# cmv_s.net
KiCad netlist of a schematic drawn in EAGLE
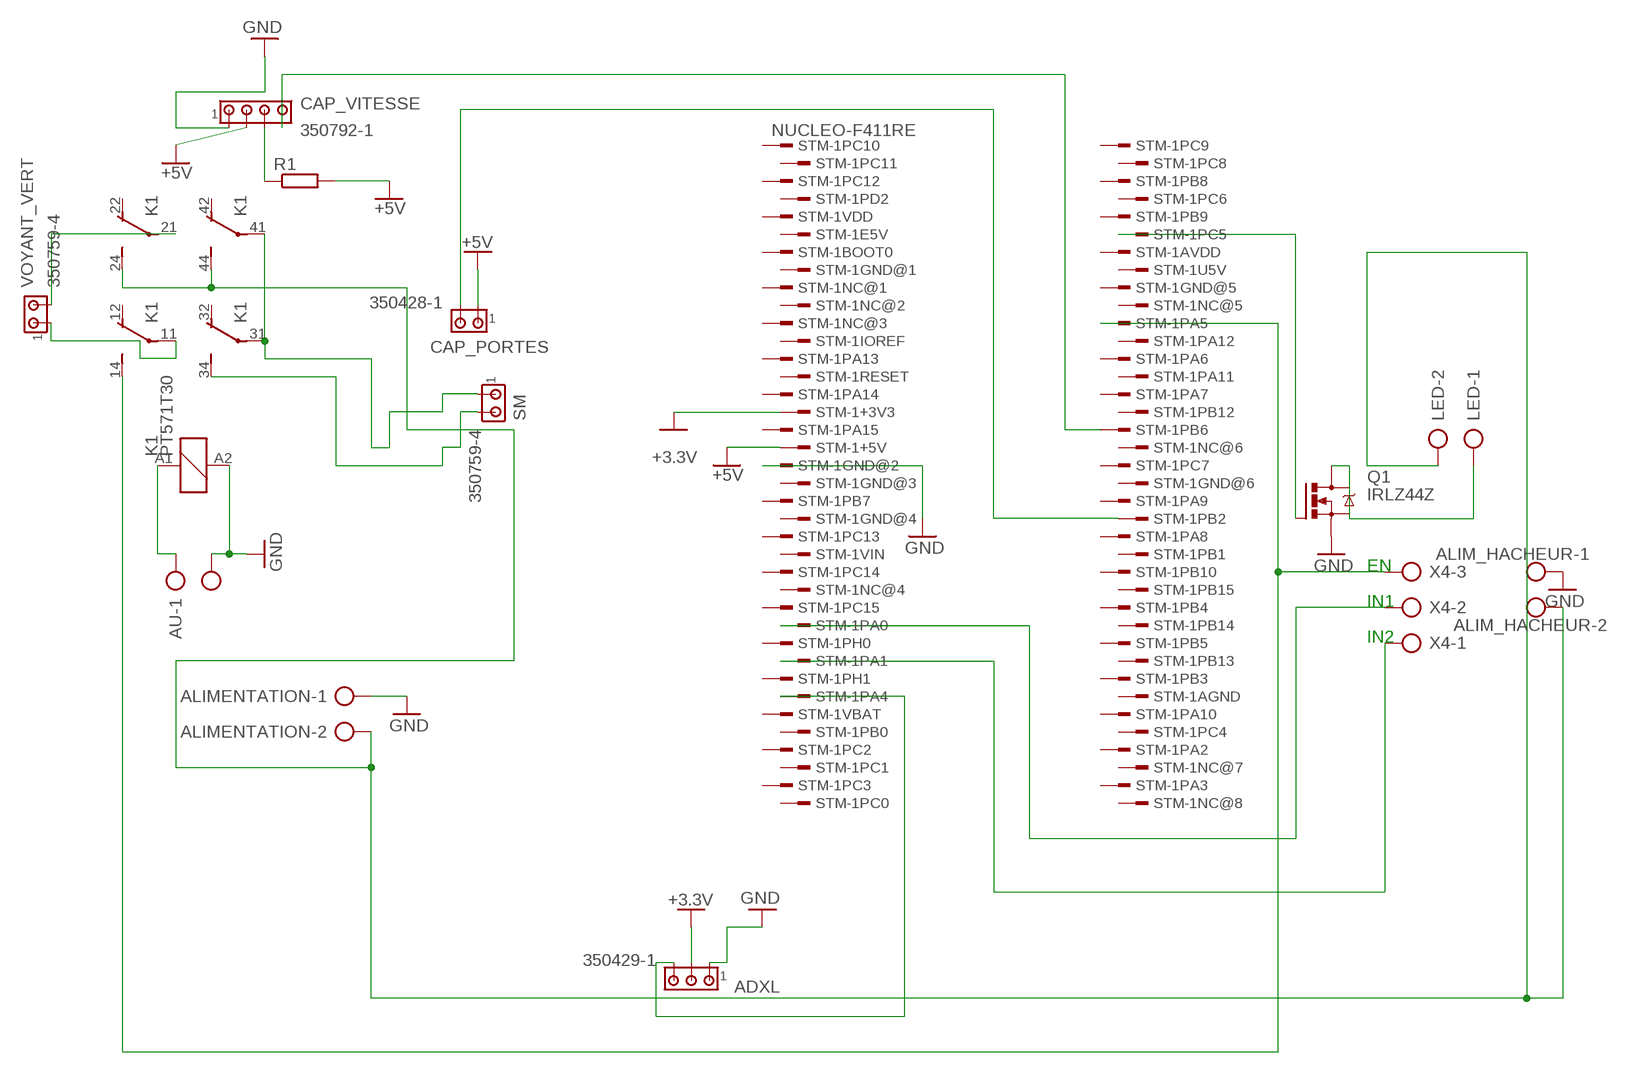
[diagram p0: schematic, sheet 1]

(export (version "E")
  (design (tool "Eeschema 10.0.6"))
  (components
    (comp (ref "ADXL")
      (value "350429-1")
      (footprint "eagle-import:350429-1")
      (libsource (lib "eagle-import") (part "350429-1"))
    )
    (comp (ref "ALIMENTATION")
      (value "AK300/2")
      (footprint "eagle-import:AK300_2")
      (libsource (lib "eagle-import") (part "AK300/2"))
    )
    (comp (ref "ALIM_HACHEUR")
      (value "AK300/2")
      (footprint "eagle-import:AK300_2")
      (libsource (lib "eagle-import") (part "AK300/2"))
    )
    (comp (ref "AU")
      (value "AK300/2")
      (footprint "eagle-import:AK300_2")
      (libsource (lib "eagle-import") (part "AK300/2"))
    )
    (comp (ref "CAP_PORTES")
      (value "350428-1")
      (footprint "eagle-import:350428-1")
      (libsource (lib "eagle-import") (part "350428-1"))
    )
    (comp (ref "CAP_VITESSE")
      (value "350792-1")
      (footprint "eagle-import:350792-1")
      (libsource (lib "eagle-import") (part "350792-1"))
    )
    (comp (ref "K1")
      (value "PT571T30")
      (footprint "eagle-import:PT-4")
      (libsource (lib "eagle-import") (part "PT571T30"))
    )
    (comp (ref "LED")
      (value "AK300/2")
      (footprint "eagle-import:AK300_2")
      (libsource (lib "eagle-import") (part "AK300/2"))
    )
    (comp (ref "Q1")
      (value "IRLZ44Z")
      (footprint "eagle-import:TO220BH")
      (libsource (lib "eagle-import") (part "IRLZ44Z"))
    )
    (comp (ref "R1")
      (value "R-EU_0204/7")
      (footprint "eagle-import:0204_7")
      (libsource (lib "eagle-import") (part "R-EU_0204/7"))
    )
    (comp (ref "SM")
      (value "350759-4")
      (footprint "eagle-import:350759-4")
      (libsource (lib "eagle-import") (part "350759-4"))
    )
    (comp (ref "STM-1")
      (value "NUCLEO-F411RE")
      (footprint "eagle-import:CONN_STM32_NUCLEO")
      (libsource (lib "eagle-import") (part "NUCLEO-F411RE"))
    )
    (comp (ref "VOYANT_VERT")
      (value "350759-4")
      (footprint "eagle-import:350759-4")
      (libsource (lib "eagle-import") (part "350759-4"))
    )
    (comp (ref "X4")
      (value "AK300/3")
      (footprint "eagle-import:AK300_3")
      (libsource (lib "eagle-import") (part "AK300/3"))
    )
  )
  (nets
    (net (code "1") (name "+3.3V") (class "Default")
      (node (ref "ADXL") (pin "2") (pinfunction "2_2") (pintype "passive"))
      (node (ref "STM-1") (pin "16") (pinfunction "1_16") (pintype "passive"))
    )
    (net (code "2") (name "+5V") (class "Default")
      (node (ref "CAP_PORTES") (pin "1") (pinfunction "1_1") (pintype "passive"))
      (node (ref "CAP_VITESSE") (pin "2") (pinfunction "2_2") (pintype "passive"))
      (node (ref "R1") (pin "2") (pinfunction "2_2") (pintype "passive"))
      (node (ref "STM-1") (pin "18") (pinfunction "1_18") (pintype "passive"))
    )
    (net (code "3") (name "GND") (class "Default")
      (node (ref "ADXL") (pin "1") (pinfunction "1_1") (pintype "passive"))
      (node (ref "ALIMENTATION") (pin "1") (pinfunction "KL_1") (pintype "passive"))
      (node (ref "ALIM_HACHEUR") (pin "1") (pinfunction "KL_1") (pintype "passive"))
      (node (ref "AU") (pin "2") (pinfunction "KL_2") (pintype "passive"))
      (node (ref "CAP_VITESSE") (pin "1") (pinfunction "1_1") (pintype "passive"))
      (node (ref "K1") (pin "A2") (pinfunction "2_A2") (pintype "passive"))
      (node (ref "Q1") (pin "S") (pinfunction "S_S") (pintype "passive"))
      (node (ref "STM-1") (pin "19") (pinfunction "1_19") (pintype "passive"))
    )
    (net (code "4") (name "Net-(ALIMENTATIONB-KL)") (class "Default")
      (node (ref "ALIMENTATION") (pin "2") (pinfunction "KL_2") (pintype "passive"))
      (node (ref "ALIM_HACHEUR") (pin "2") (pinfunction "KL_2") (pintype "passive"))
      (node (ref "K1") (pin "24") (pinfunction "S_24") (pintype "passive"))
      (node (ref "K1") (pin "44") (pinfunction "S_44") (pintype "passive"))
      (node (ref "LED") (pin "2") (pinfunction "KL_2") (pintype "passive"))
    )
    (net (code "5") (name "Net-(AUA-KL)") (class "Default")
      (node (ref "AU") (pin "1") (pinfunction "KL_1") (pintype "passive"))
      (node (ref "K1") (pin "A1") (pinfunction "1_A1") (pintype "passive"))
    )
    (net (code "6") (name "Net-(CAP_VITESSE-Pad3)") (class "Default")
      (node (ref "CAP_VITESSE") (pin "3") (pinfunction "3_3") (pintype "passive"))
      (node (ref "R1") (pin "1") (pinfunction "1_1") (pintype "passive"))
    )
    (net (code "7") (name "Net-(K1B-P)") (class "Default")
      (node (ref "K1") (pin "11") (pinfunction "P_11") (pintype "passive"))
      (node (ref "VOYANT_VERT") (pin "1") (pinfunction "1_1") (pintype "passive"))
    )
    (net (code "8") (name "Net-(K1B-S)") (class "Default")
      (node (ref "K1") (pin "14") (pinfunction "S_14") (pintype "passive"))
      (node (ref "STM-1") (pin "49") (pinfunction "1_49") (pintype "passive"))
      (node (ref "X4") (pin "3") (pinfunction "KL_3") (pintype "passive"))
    )
    (net (code "9") (name "Net-(K1C-P)") (class "Default")
      (node (ref "K1") (pin "21") (pinfunction "P_21") (pintype "passive"))
      (node (ref "VOYANT_VERT") (pin "2") (pinfunction "2_2") (pintype "passive"))
    )
    (net (code "10") (name "Net-(K1D-P)") (class "Default")
      (node (ref "K1") (pin "31") (pinfunction "P_31") (pintype "passive"))
      (node (ref "K1") (pin "41") (pinfunction "P_41") (pintype "passive"))
      (node (ref "SM") (pin "1") (pinfunction "1_1") (pintype "passive"))
    )
    (net (code "11") (name "Net-(K1D-S)") (class "Default")
      (node (ref "K1") (pin "34") (pinfunction "S_34") (pintype "passive"))
      (node (ref "SM") (pin "2") (pinfunction "2_2") (pintype "passive"))
    )
    (net (code "12") (name "Net-(LEDA-KL)") (class "Default")
      (node (ref "LED") (pin "1") (pinfunction "KL_1") (pintype "passive"))
      (node (ref "Q1") (pin "D") (pinfunction "D_D") (pintype "passive"))
    )
    (net (code "13") (name "Net-(STM-1AF-1)") (class "Default")
      (node (ref "ADXL") (pin "3") (pinfunction "3_3") (pintype "passive"))
      (node (ref "STM-1") (pin "32") (pinfunction "1_32") (pintype "passive"))
    )
    (net (code "14") (name "Net-(STM-1AS-1)") (class "Default")
      (node (ref "CAP_PORTES") (pin "2") (pinfunction "2_2") (pintype "passive"))
      (node (ref "STM-1") (pin "60") (pinfunction "1_60") (pintype "passive"))
    )
    (net (code "15") (name "Net-(STM-1AW-1)") (class "Default")
      (node (ref "CAP_VITESSE") (pin "4") (pinfunction "4_4") (pintype "passive"))
      (node (ref "STM-1") (pin "55") (pinfunction "1_55") (pintype "passive"))
    )
    (net (code "16") (name "Net-(STM-1BL-1)") (class "Default")
      (node (ref "Q1") (pin "G") (pinfunction "G_G") (pintype "passive"))
      (node (ref "STM-1") (pin "44") (pinfunction "1_44") (pintype "passive"))
    )
    (net (code "17") (name "Net-(STM-1V-1)") (class "Default")
      (node (ref "STM-1") (pin "28") (pinfunction "1_28") (pintype "passive"))
      (node (ref "X4") (pin "2") (pinfunction "KL_2") (pintype "passive"))
    )
    (net (code "18") (name "Net-(STM-1W-1)") (class "Default")
      (node (ref "STM-1") (pin "30") (pinfunction "1_30") (pintype "passive"))
      (node (ref "X4") (pin "1") (pinfunction "KL_1") (pintype "passive"))
    )
    (net (code "19") (name "unconnected-(K1B-O-Pad12)") (class "Default")
      (node (ref "K1") (pin "12") (pinfunction "O_12") (pintype "passive"))
    )
    (net (code "20") (name "unconnected-(K1C-O-Pad22)") (class "Default")
      (node (ref "K1") (pin "22") (pinfunction "O_22") (pintype "passive"))
    )
    (net (code "21") (name "unconnected-(K1D-O-Pad32)") (class "Default")
      (node (ref "K1") (pin "32") (pinfunction "O_32") (pintype "passive"))
    )
    (net (code "22") (name "unconnected-(K1E-O-Pad42)") (class "Default")
      (node (ref "K1") (pin "42") (pinfunction "O_42") (pintype "passive"))
    )
    (net (code "23") (name "unconnected-(STM-1-Pad1)") (class "Default")
      (node (ref "STM-1") (pin "1") (pinfunction "1_1") (pintype "passive"))
    )
    (net (code "24") (name "unconnected-(STM-1AA-1-Pad13)") (class "Default")
      (node (ref "STM-1") (pin "13") (pinfunction "1_13") (pintype "passive"))
    )
    (net (code "25") (name "unconnected-(STM-1AB-1-Pad15)") (class "Default")
      (node (ref "STM-1") (pin "15") (pinfunction "1_15") (pintype "passive"))
    )
    (net (code "26") (name "unconnected-(STM-1AC-1-Pad17)") (class "Default")
      (node (ref "STM-1") (pin "17") (pinfunction "1_17") (pintype "passive"))
    )
    (net (code "27") (name "unconnected-(STM-1AD-1-Pad73)") (class "Default")
      (node (ref "STM-1") (pin "73") (pinfunction "1_73") (pintype "passive"))
    )
    (net (code "28") (name "unconnected-(STM-1AE-1-Pad75)") (class "Default")
      (node (ref "STM-1") (pin "75") (pinfunction "1_75") (pintype "passive"))
    )
    (net (code "29") (name "unconnected-(STM-1AH-1-Pad51)") (class "Default")
      (node (ref "STM-1") (pin "51") (pinfunction "1_51") (pintype "passive"))
    )
    (net (code "30") (name "unconnected-(STM-1AI-1-Pad53)") (class "Default")
      (node (ref "STM-1") (pin "53") (pinfunction "1_53") (pintype "passive"))
    )
    (net (code "31") (name "unconnected-(STM-1AJ-1-Pad61)") (class "Default")
      (node (ref "STM-1") (pin "61") (pinfunction "1_61") (pintype "passive"))
    )
    (net (code "32") (name "unconnected-(STM-1AK-1-Pad59)") (class "Default")
      (node (ref "STM-1") (pin "59") (pinfunction "1_59") (pintype "passive"))
    )
    (net (code "33") (name "unconnected-(STM-1AL-1-Pad34)") (class "Default")
      (node (ref "STM-1") (pin "34") (pinfunction "1_34") (pintype "passive"))
    )
    (net (code "34") (name "unconnected-(STM-1AM-1-Pad62)") (class "Default")
      (node (ref "STM-1") (pin "62") (pinfunction "1_62") (pintype "passive"))
    )
    (net (code "35") (name "unconnected-(STM-1AN-1-Pad63)") (class "Default")
      (node (ref "STM-1") (pin "63") (pinfunction "1_63") (pintype "passive"))
    )
    (net (code "36") (name "unconnected-(STM-1AO-1-Pad54)") (class "Default")
      (node (ref "STM-1") (pin "54") (pinfunction "1_54") (pintype "passive"))
    )
    (net (code "37") (name "unconnected-(STM-1AP-1-Pad68)") (class "Default")
      (node (ref "STM-1") (pin "68") (pinfunction "1_68") (pintype "passive"))
    )
    (net (code "38") (name "unconnected-(STM-1AQ-1-Pad66)") (class "Default")
      (node (ref "STM-1") (pin "66") (pinfunction "1_66") (pintype "passive"))
    )
    (net (code "39") (name "unconnected-(STM-1AR-1-Pad64)") (class "Default")
      (node (ref "STM-1") (pin "64") (pinfunction "1_64") (pintype "passive"))
    )
    (net (code "40") (name "unconnected-(STM-1AT-1-Pad69)") (class "Default")
      (node (ref "STM-1") (pin "69") (pinfunction "1_69") (pintype "passive"))
    )
    (net (code "41") (name "unconnected-(STM-1AU-1-Pad65)") (class "Default")
      (node (ref "STM-1") (pin "65") (pinfunction "1_65") (pintype "passive"))
    )
    (net (code "42") (name "unconnected-(STM-1AV-1-Pad67)") (class "Default")
      (node (ref "STM-1") (pin "67") (pinfunction "1_67") (pintype "passive"))
    )
    (net (code "43") (name "unconnected-(STM-1AX-1-Pad21)") (class "Default")
      (node (ref "STM-1") (pin "21") (pinfunction "1_21") (pintype "passive"))
    )
    (net (code "44") (name "unconnected-(STM-1AY-1-Pad41)") (class "Default")
      (node (ref "STM-1") (pin "41") (pinfunction "1_41") (pintype "passive"))
    )
    (net (code "45") (name "unconnected-(STM-1AZ-1-Pad43)") (class "Default")
      (node (ref "STM-1") (pin "43") (pinfunction "1_43") (pintype "passive"))
    )
    (net (code "46") (name "unconnected-(STM-1BA-1-Pad38)") (class "Default")
      (node (ref "STM-1") (pin "38") (pinfunction "1_38") (pintype "passive"))
    )
    (net (code "47") (name "unconnected-(STM-1BB-1-Pad36)") (class "Default")
      (node (ref "STM-1") (pin "36") (pinfunction "1_36") (pintype "passive"))
    )
    (net (code "48") (name "unconnected-(STM-1BD-1-Pad2)") (class "Default")
      (node (ref "STM-1") (pin "2") (pinfunction "1_2") (pintype "passive"))
    )
    (net (code "49") (name "unconnected-(STM-1BE-1-Pad3)") (class "Default")
      (node (ref "STM-1") (pin "3") (pinfunction "1_3") (pintype "passive"))
    )
    (net (code "50") (name "unconnected-(STM-1BF-1-Pad23)") (class "Default")
      (node (ref "STM-1") (pin "23") (pinfunction "1_23") (pintype "passive"))
    )
    (net (code "51") (name "unconnected-(STM-1BG-1-Pad25)") (class "Default")
      (node (ref "STM-1") (pin "25") (pinfunction "1_25") (pintype "passive"))
    )
    (net (code "52") (name "unconnected-(STM-1BH-1-Pad27)") (class "Default")
      (node (ref "STM-1") (pin "27") (pinfunction "1_27") (pintype "passive"))
    )
    (net (code "53") (name "unconnected-(STM-1BI-1-Pad35)") (class "Default")
      (node (ref "STM-1") (pin "35") (pinfunction "1_35") (pintype "passive"))
    )
    (net (code "54") (name "unconnected-(STM-1BJ-1-Pad37)") (class "Default")
      (node (ref "STM-1") (pin "37") (pinfunction "1_37") (pintype "passive"))
    )
    (net (code "55") (name "unconnected-(STM-1BK-1-Pad72)") (class "Default")
      (node (ref "STM-1") (pin "72") (pinfunction "1_72") (pintype "passive"))
    )
    (net (code "56") (name "unconnected-(STM-1BM-1-Pad42)") (class "Default")
      (node (ref "STM-1") (pin "42") (pinfunction "1_42") (pintype "passive"))
    )
    (net (code "57") (name "unconnected-(STM-1BN-1-Pad57)") (class "Default")
      (node (ref "STM-1") (pin "57") (pinfunction "1_57") (pintype "passive"))
    )
    (net (code "58") (name "unconnected-(STM-1BO-1-Pad40)") (class "Default")
      (node (ref "STM-1") (pin "40") (pinfunction "1_40") (pintype "passive"))
    )
    (net (code "59") (name "unconnected-(STM-1BP-1-Pad39)") (class "Default")
      (node (ref "STM-1") (pin "39") (pinfunction "1_39") (pintype "passive"))
    )
    (net (code "60") (name "unconnected-(STM-1BQ-1-Pad4)") (class "Default")
      (node (ref "STM-1") (pin "4") (pinfunction "1_4") (pintype "passive"))
    )
    (net (code "61") (name "unconnected-(STM-1BR-1-Pad29)") (class "Default")
      (node (ref "STM-1") (pin "29") (pinfunction "1_29") (pintype "passive"))
    )
    (net (code "62") (name "unconnected-(STM-1BS-1-Pad31)") (class "Default")
      (node (ref "STM-1") (pin "31") (pinfunction "1_31") (pintype "passive"))
    )
    (net (code "63") (name "unconnected-(STM-1BT-1-Pad14)") (class "Default")
      (node (ref "STM-1") (pin "14") (pinfunction "1_14") (pintype "passive"))
    )
    (net (code "64") (name "unconnected-(STM-1BU-1-Pad46)") (class "Default")
      (node (ref "STM-1") (pin "46") (pinfunction "1_46") (pintype "passive"))
    )
    (net (code "65") (name "unconnected-(STM-1BV-1-Pad33)") (class "Default")
      (node (ref "STM-1") (pin "33") (pinfunction "1_33") (pintype "passive"))
    )
    (net (code "66") (name "unconnected-(STM-1BW-1-Pad5)") (class "Default")
      (node (ref "STM-1") (pin "5") (pinfunction "1_5") (pintype "passive"))
    )
    (net (code "67") (name "unconnected-(STM-1BX-1-Pad24)") (class "Default")
      (node (ref "STM-1") (pin "24") (pinfunction "1_24") (pintype "passive"))
    )
    (net (code "68") (name "unconnected-(STM-1C-1-Pad70)") (class "Default")
      (node (ref "STM-1") (pin "70") (pinfunction "1_70") (pintype "passive"))
    )
    (net (code "69") (name "unconnected-(STM-1D-1-Pad45)") (class "Default")
      (node (ref "STM-1") (pin "45") (pinfunction "1_45") (pintype "passive"))
    )
    (net (code "70") (name "unconnected-(STM-1E-1-Pad7)") (class "Default")
      (node (ref "STM-1") (pin "7") (pinfunction "1_7") (pintype "passive"))
    )
    (net (code "71") (name "unconnected-(STM-1F-1-Pad6)") (class "Default")
      (node (ref "STM-1") (pin "6") (pinfunction "1_6") (pintype "passive"))
    )
    (net (code "72") (name "unconnected-(STM-1G-1-Pad8)") (class "Default")
      (node (ref "STM-1") (pin "8") (pinfunction "1_8") (pintype "passive"))
    )
    (net (code "73") (name "unconnected-(STM-1I-1-Pad20)") (class "Default")
      (node (ref "STM-1") (pin "20") (pinfunction "1_20") (pintype "passive"))
    )
    (net (code "74") (name "unconnected-(STM-1J-1-Pad22)") (class "Default")
      (node (ref "STM-1") (pin "22") (pinfunction "1_22") (pintype "passive"))
    )
    (net (code "75") (name "unconnected-(STM-1K-1-Pad47)") (class "Default")
      (node (ref "STM-1") (pin "47") (pinfunction "1_47") (pintype "passive"))
    )
    (net (code "76") (name "unconnected-(STM-1L-1-Pad58)") (class "Default")
      (node (ref "STM-1") (pin "58") (pinfunction "1_58") (pintype "passive"))
    )
    (net (code "77") (name "unconnected-(STM-1M-1-Pad12)") (class "Default")
      (node (ref "STM-1") (pin "12") (pinfunction "1_12") (pintype "passive"))
    )
    (net (code "78") (name "unconnected-(STM-1N-1-Pad9)") (class "Default")
      (node (ref "STM-1") (pin "9") (pinfunction "1_9") (pintype "passive"))
    )
    (net (code "79") (name "unconnected-(STM-1O-1-Pad10)") (class "Default")
      (node (ref "STM-1") (pin "10") (pinfunction "1_10") (pintype "passive"))
    )
    (net (code "80") (name "unconnected-(STM-1P-1-Pad11)") (class "Default")
      (node (ref "STM-1") (pin "11") (pinfunction "1_11") (pintype "passive"))
    )
    (net (code "81") (name "unconnected-(STM-1Q-1-Pad26)") (class "Default")
      (node (ref "STM-1") (pin "26") (pinfunction "1_26") (pintype "passive"))
    )
    (net (code "82") (name "unconnected-(STM-1R-1-Pad48)") (class "Default")
      (node (ref "STM-1") (pin "48") (pinfunction "1_48") (pintype "passive"))
    )
    (net (code "83") (name "unconnected-(STM-1S-1-Pad56)") (class "Default")
      (node (ref "STM-1") (pin "56") (pinfunction "1_56") (pintype "passive"))
    )
    (net (code "84") (name "unconnected-(STM-1T-1-Pad74)") (class "Default")
      (node (ref "STM-1") (pin "74") (pinfunction "1_74") (pintype "passive"))
    )
    (net (code "85") (name "unconnected-(STM-1U-1-Pad76)") (class "Default")
      (node (ref "STM-1") (pin "76") (pinfunction "1_76") (pintype "passive"))
    )
    (net (code "86") (name "unconnected-(STM-1X-1-Pad71)") (class "Default")
      (node (ref "STM-1") (pin "71") (pinfunction "1_71") (pintype "passive"))
    )
    (net (code "87") (name "unconnected-(STM-1Y-1-Pad52)") (class "Default")
      (node (ref "STM-1") (pin "52") (pinfunction "1_52") (pintype "passive"))
    )
    (net (code "88") (name "unconnected-(STM-1Z-1-Pad50)") (class "Default")
      (node (ref "STM-1") (pin "50") (pinfunction "1_50") (pintype "passive"))
    )
  )
)
